# EPS_5V_Buck-Converter.net
KiCad netlist of a schematic drawn in Altium Designer
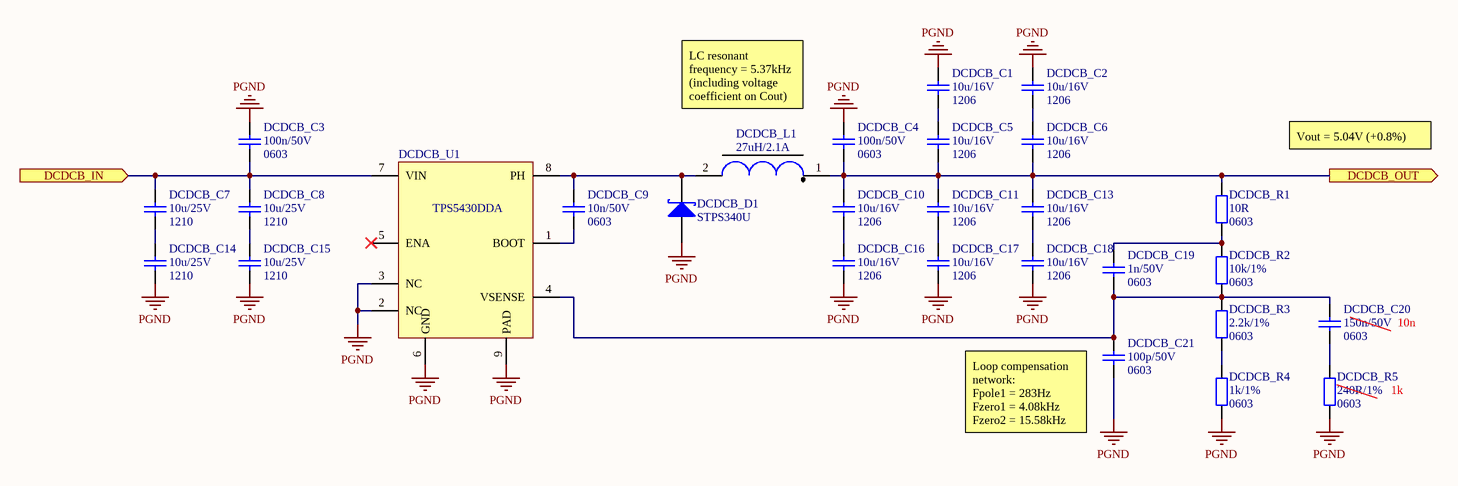
[diagram p0: EPS_5V_Buck-Converter.SchDoc]

(export (version "E")
  (design (tool "Eeschema 10.0.6"))
  (components
    (comp (ref "DCDCB_C1")
      (value "10u/16V")
      (footprint "SMD_Capacitor_1206")
      (description "Ceramic Cap Kemet COTS 10u/16V X7R 1206")
      (fields
        (field (name "MANUFACTURERPARTNUMBER") "C1206T106K4RACTU")
        (field (name "MANUFACTURER") "Kemet")
        (field (name "PACKGE") "1206")
      )
      (libsource (lib "capacitors") (part "Cer_C1206T106K4RACTU"))
    )
    (comp (ref "DCDCB_C2")
      (value "10u/16V")
      (footprint "SMD_Capacitor_1206")
      (description "Ceramic Cap Kemet COTS 10u/16V X7R 1206")
      (fields
        (field (name "MANUFACTURERPARTNUMBER") "C1206T106K4RACTU")
        (field (name "MANUFACTURER") "Kemet")
        (field (name "PACKGE") "1206")
      )
      (libsource (lib "capacitors") (part "Cer_C1206T106K4RACTU"))
    )
    (comp (ref "DCDCB_C3")
      (value "100n/50V")
      (footprint "SMD_Capacitor_0603")
      (description "Ceramic Cap Murata Automotive 100n/50V X7R 0603")
      (fields
        (field (name "MANUFACTURER") "Murata")
        (field (name "MANUFACTURERPARTNUMBER") "GCJ188R71H104KA12D")
        (field (name "PACKAGE") "0603")
      )
      (libsource (lib "capacitors") (part "Cer_GCJ188R71H104KA12D"))
    )
    (comp (ref "DCDCB_C4")
      (value "100n/50V")
      (footprint "SMD_Capacitor_0603")
      (description "Ceramic Cap Murata Automotive 100n/50V X7R 0603")
      (fields
        (field (name "MANUFACTURER") "Murata")
        (field (name "MANUFACTURERPARTNUMBER") "GCJ188R71H104KA12D")
        (field (name "PACKAGE") "0603")
      )
      (libsource (lib "capacitors") (part "Cer_GCJ188R71H104KA12D"))
    )
    (comp (ref "DCDCB_C5")
      (value "10u/16V")
      (footprint "SMD_Capacitor_1206")
      (description "Ceramic Cap Kemet COTS 10u/16V X7R 1206")
      (fields
        (field (name "MANUFACTURERPARTNUMBER") "C1206T106K4RACTU")
        (field (name "MANUFACTURER") "Kemet")
        (field (name "PACKGE") "1206")
      )
      (libsource (lib "capacitors") (part "Cer_C1206T106K4RACTU"))
    )
    (comp (ref "DCDCB_C6")
      (value "10u/16V")
      (footprint "SMD_Capacitor_1206")
      (description "Ceramic Cap Kemet COTS 10u/16V X7R 1206")
      (fields
        (field (name "MANUFACTURERPARTNUMBER") "C1206T106K4RACTU")
        (field (name "MANUFACTURER") "Kemet")
        (field (name "PACKGE") "1206")
      )
      (libsource (lib "capacitors") (part "Cer_C1206T106K4RACTU"))
    )
    (comp (ref "DCDCB_C7")
      (value "10u/25V")
      (footprint "SMD_Capacitor_1210")
      (description "Ceramic Cap Murata Automotive 10u/25V X7R 1210")
      (fields
        (field (name "MANUFACTURER") "Murata")
        (field (name "MANUFACTURERPARTNUMBER") "GCJ32ER71E106KA12L")
        (field (name "PACKAGE") "1210")
      )
      (libsource (lib "capacitors") (part "Cer_GCJ32ER71E106KA12L"))
    )
    (comp (ref "DCDCB_C8")
      (value "10u/25V")
      (footprint "SMD_Capacitor_1210")
      (description "Ceramic Cap Murata Automotive 10u/25V X7R 1210")
      (fields
        (field (name "MANUFACTURER") "Murata")
        (field (name "MANUFACTURERPARTNUMBER") "GCJ32ER71E106KA12L")
        (field (name "PACKAGE") "1210")
      )
      (libsource (lib "capacitors") (part "Cer_GCJ32ER71E106KA12L"))
    )
    (comp (ref "DCDCB_C9")
      (value "10n/50V")
      (footprint "SMD_Capacitor_0603")
      (description "Cap")
      (fields (field (name "PACKAGE") "0603"))
      (libsource (lib "capacitors") (part "Cap"))
    )
    (comp (ref "DCDCB_C10")
      (value "10u/16V")
      (footprint "SMD_Capacitor_1206")
      (description "Ceramic Cap Kemet COTS 10u/16V X7R 1206")
      (fields
        (field (name "MANUFACTURERPARTNUMBER") "C1206T106K4RACTU")
        (field (name "MANUFACTURER") "Kemet")
        (field (name "PACKGE") "1206")
      )
      (libsource (lib "capacitors") (part "Cer_C1206T106K4RACTU"))
    )
    (comp (ref "DCDCB_C11")
      (value "10u/16V")
      (footprint "SMD_Capacitor_1206")
      (description "Ceramic Cap Kemet COTS 10u/16V X7R 1206")
      (fields
        (field (name "MANUFACTURERPARTNUMBER") "C1206T106K4RACTU")
        (field (name "MANUFACTURER") "Kemet")
        (field (name "PACKGE") "1206")
      )
      (libsource (lib "capacitors") (part "Cer_C1206T106K4RACTU"))
    )
    (comp (ref "DCDCB_C13")
      (value "10u/16V")
      (footprint "SMD_Capacitor_1206")
      (description "Ceramic Cap Kemet COTS 10u/16V X7R 1206")
      (fields
        (field (name "MANUFACTURERPARTNUMBER") "C1206T106K4RACTU")
        (field (name "MANUFACTURER") "Kemet")
        (field (name "PACKGE") "1206")
      )
      (libsource (lib "capacitors") (part "Cer_C1206T106K4RACTU"))
    )
    (comp (ref "DCDCB_C14")
      (value "10u/25V")
      (footprint "SMD_Capacitor_1210")
      (description "Ceramic Cap Murata Automotive 10u/25V X7R 1210")
      (fields
        (field (name "MANUFACTURER") "Murata")
        (field (name "MANUFACTURERPARTNUMBER") "GCJ32ER71E106KA12L")
        (field (name "PACKAGE") "1210")
      )
      (libsource (lib "capacitors") (part "Cer_GCJ32ER71E106KA12L"))
    )
    (comp (ref "DCDCB_C15")
      (value "10u/25V")
      (footprint "SMD_Capacitor_1210")
      (description "Ceramic Cap Murata Automotive 10u/25V X7R 1210")
      (fields
        (field (name "MANUFACTURER") "Murata")
        (field (name "MANUFACTURERPARTNUMBER") "GCJ32ER71E106KA12L")
        (field (name "PACKAGE") "1210")
      )
      (libsource (lib "capacitors") (part "Cer_GCJ32ER71E106KA12L"))
    )
    (comp (ref "DCDCB_C16")
      (value "10u/16V")
      (footprint "SMD_Capacitor_1206")
      (description "Ceramic Cap Kemet COTS 10u/16V X7R 1206")
      (fields
        (field (name "MANUFACTURERPARTNUMBER") "C1206T106K4RACTU")
        (field (name "MANUFACTURER") "Kemet")
        (field (name "PACKGE") "1206")
      )
      (libsource (lib "capacitors") (part "Cer_C1206T106K4RACTU"))
    )
    (comp (ref "DCDCB_C17")
      (value "10u/16V")
      (footprint "SMD_Capacitor_1206")
      (description "Ceramic Cap Kemet COTS 10u/16V X7R 1206")
      (fields
        (field (name "MANUFACTURERPARTNUMBER") "C1206T106K4RACTU")
        (field (name "MANUFACTURER") "Kemet")
        (field (name "PACKGE") "1206")
      )
      (libsource (lib "capacitors") (part "Cer_C1206T106K4RACTU"))
    )
    (comp (ref "DCDCB_C18")
      (value "10u/16V")
      (footprint "SMD_Capacitor_1206")
      (description "Ceramic Cap Kemet COTS 10u/16V X7R 1206")
      (fields
        (field (name "MANUFACTURERPARTNUMBER") "C1206T106K4RACTU")
        (field (name "MANUFACTURER") "Kemet")
        (field (name "PACKGE") "1206")
      )
      (libsource (lib "capacitors") (part "Cer_C1206T106K4RACTU"))
    )
    (comp (ref "DCDCB_C19")
      (value "1n/50V")
      (footprint "SMD_Capacitor_0603")
      (description "Cap")
      (fields (field (name "PACKAGE") "0603"))
      (libsource (lib "capacitors") (part "Cap"))
    )
    (comp (ref "DCDCB_C20")
      (value "150n/50V")
      (footprint "SMD_Capacitor_0603")
      (description "Ceramic Cap Murata Automotive 150n/50V X7R 0603")
      (fields
        (field (name "MANUFACTURER") "Murata")
        (field (name "MANUFACTURERPARTNUMBER") "GCM188R71H154KA64D")
        (field (name "PACKAGE") "0603")
      )
      (libsource (lib "capacitors") (part "Cer_GCM188R71H154KA64D"))
    )
    (comp (ref "DCDCB_C21")
      (value "100p/50V")
      (footprint "SMD_Capacitor_0603")
      (description "Cap")
      (fields (field (name "PACKAGE") "0603"))
      (libsource (lib "capacitors") (part "Cap"))
    )
    (comp (ref "DCDCB_D1")
      (value "STPS340U")
      (footprint "DO-214AA")
      (description "3A/40V Power Schottky Rectifier.")
      (fields (field (name "MANUFACTURER") "STMicroelectronics"))
      (libsource (lib "diodes") (part "STPS340x"))
    )
    (comp (ref "DCDCB_L1")
      (value "27uH/2.1A")
      (footprint "Coilcraft_MSS1260")
      (description "Coilcraft MSS1260 Inductor, L=27uH, Irise20deg=2.1A, ESR=50mR, SRF=13MHz.")
      (fields
        (field (name "MANUFACTURER") "Coilcraft")
        (field (name "MANUFACTURERPARTNUMBER") "MSS1260-273MLx")
      )
      (libsource (lib "inductors") (part "MSS1260-273MLx"))
    )
    (comp (ref "DCDCB_R1")
      (value "10R")
      (footprint "SMD_Resistor_0603")
      (fields (field (name "PACKAGE") "0603"))
      (libsource (lib "resistors") (part "Res"))
    )
    (comp (ref "DCDCB_R2")
      (value "10k/1%")
      (footprint "SMD_Resistor_0603")
      (fields (field (name "PACKAGE") "0603"))
      (libsource (lib "resistors") (part "Res"))
    )
    (comp (ref "DCDCB_R3")
      (value "2.2k/1%")
      (footprint "SMD_Resistor_0603")
      (fields (field (name "PACKAGE") "0603"))
      (libsource (lib "resistors") (part "Res"))
    )
    (comp (ref "DCDCB_R4")
      (value "1k/1%")
      (footprint "SMD_Resistor_0603")
      (fields (field (name "PACKAGE") "0603"))
      (libsource (lib "resistors") (part "Res"))
    )
    (comp (ref "DCDCB_R5")
      (value "240R/1%")
      (footprint "SMD_Resistor_0603")
      (fields (field (name "PACKAGE") "0603"))
      (libsource (lib "resistors") (part "Res"))
    )
    (comp (ref "DCDCB_U1")
      (value "TPS5430DDA")
      (footprint "DDA-9")
      (description "TPS5430 3-A, Wide Input Range, Step-Down Converter")
      (fields (field (name "MANUFACTURER") "Texas Instruments"))
      (libsource (lib "microcircuits") (part "TPS5430"))
    )
  )
  (nets
    (net (code "1") (name "/DCDCB_IN") (class "Default")
      (node (ref "DCDCB_C3") (pin "1") (pinfunction "1_1") (pintype "passive"))
      (node (ref "DCDCB_C7") (pin "1") (pinfunction "1_1") (pintype "passive"))
      (node (ref "DCDCB_C8") (pin "1") (pinfunction "1_1") (pintype "passive"))
      (node (ref "DCDCB_U1") (pin "7") (pinfunction "VIN_7") (pintype "passive"))
    )
    (net (code "2") (name "/DCDCB_OUT") (class "Default")
      (node (ref "DCDCB_C10") (pin "1") (pinfunction "1_1") (pintype "passive"))
      (node (ref "DCDCB_C11") (pin "1") (pinfunction "1_1") (pintype "passive"))
      (node (ref "DCDCB_C13") (pin "1") (pinfunction "1_1") (pintype "passive"))
      (node (ref "DCDCB_C4") (pin "1") (pinfunction "1_1") (pintype "passive"))
      (node (ref "DCDCB_C5") (pin "2") (pinfunction "2_2") (pintype "passive"))
      (node (ref "DCDCB_C6") (pin "2") (pinfunction "2_2") (pintype "passive"))
      (node (ref "DCDCB_L1") (pin "1") (pinfunction "1_1") (pintype "passive"))
      (node (ref "DCDCB_R1") (pin "2") (pinfunction "2_2") (pintype "passive"))
    )
    (net (code "3") (name "Net-(DCDCB_C1-Pad2)") (class "Default")
      (node (ref "DCDCB_C1") (pin "2") (pinfunction "2_2") (pintype "passive"))
      (node (ref "DCDCB_C5") (pin "1") (pinfunction "1_1") (pintype "passive"))
    )
    (net (code "4") (name "Net-(DCDCB_C2-Pad2)") (class "Default")
      (node (ref "DCDCB_C2") (pin "2") (pinfunction "2_2") (pintype "passive"))
      (node (ref "DCDCB_C6") (pin "1") (pinfunction "1_1") (pintype "passive"))
    )
    (net (code "5") (name "Net-(DCDCB_C10-Pad2)") (class "Default")
      (node (ref "DCDCB_C10") (pin "2") (pinfunction "2_2") (pintype "passive"))
      (node (ref "DCDCB_C16") (pin "1") (pinfunction "1_1") (pintype "passive"))
    )
    (net (code "6") (name "Net-(DCDCB_C11-Pad2)") (class "Default")
      (node (ref "DCDCB_C11") (pin "2") (pinfunction "2_2") (pintype "passive"))
      (node (ref "DCDCB_C17") (pin "1") (pinfunction "1_1") (pintype "passive"))
    )
    (net (code "7") (name "Net-(DCDCB_C13-Pad2)") (class "Default")
      (node (ref "DCDCB_C13") (pin "2") (pinfunction "2_2") (pintype "passive"))
      (node (ref "DCDCB_C18") (pin "1") (pinfunction "1_1") (pintype "passive"))
    )
    (net (code "8") (name "Net-(DCDCB_C14-Pad1)") (class "Default")
      (node (ref "DCDCB_C14") (pin "1") (pinfunction "1_1") (pintype "passive"))
      (node (ref "DCDCB_C7") (pin "2") (pinfunction "2_2") (pintype "passive"))
    )
    (net (code "9") (name "Net-(DCDCB_C15-Pad1)") (class "Default")
      (node (ref "DCDCB_C15") (pin "1") (pinfunction "1_1") (pintype "passive"))
      (node (ref "DCDCB_C8") (pin "2") (pinfunction "2_2") (pintype "passive"))
    )
    (net (code "10") (name "Net-(DCDCB_C19-Pad1)") (class "Default")
      (node (ref "DCDCB_C19") (pin "1") (pinfunction "1_1") (pintype "passive"))
      (node (ref "DCDCB_R1") (pin "1") (pinfunction "1_1") (pintype "passive"))
      (node (ref "DCDCB_R2") (pin "2") (pinfunction "2_2") (pintype "passive"))
    )
    (net (code "11") (name "Net-(DCDCB_C20-Pad2)") (class "Default")
      (node (ref "DCDCB_C20") (pin "2") (pinfunction "2_2") (pintype "passive"))
      (node (ref "DCDCB_R5") (pin "2") (pinfunction "2_2") (pintype "passive"))
    )
    (net (code "12") (name "Net-(DCDCB_R3-Pad1)") (class "Default")
      (node (ref "DCDCB_R3") (pin "1") (pinfunction "1_1") (pintype "passive"))
      (node (ref "DCDCB_R4") (pin "2") (pinfunction "2_2") (pintype "passive"))
    )
    (net (code "13") (name "Net-(DCDCB_U1-BOOT)") (class "Default")
      (node (ref "DCDCB_C9") (pin "2") (pinfunction "2_2") (pintype "passive"))
      (node (ref "DCDCB_U1") (pin "1") (pinfunction "BOOT_1") (pintype "passive"))
    )
    (net (code "14") (name "Net-(DCDCB_U1-PH)") (class "Default")
      (node (ref "DCDCB_C9") (pin "1") (pinfunction "1_1") (pintype "passive"))
      (node (ref "DCDCB_D1") (pin "K") (pinfunction "K_K") (pintype "passive"))
      (node (ref "DCDCB_L1") (pin "2") (pinfunction "2_2") (pintype "passive"))
      (node (ref "DCDCB_U1") (pin "8") (pinfunction "PH_8") (pintype "passive"))
    )
    (net (code "15") (name "Net-(DCDCB_U1-VSENSE)") (class "Default")
      (node (ref "DCDCB_C19") (pin "2") (pinfunction "2_2") (pintype "passive"))
      (node (ref "DCDCB_C20") (pin "1") (pinfunction "1_1") (pintype "passive"))
      (node (ref "DCDCB_C21") (pin "1") (pinfunction "1_1") (pintype "passive"))
      (node (ref "DCDCB_R2") (pin "1") (pinfunction "1_1") (pintype "passive"))
      (node (ref "DCDCB_R3") (pin "2") (pinfunction "2_2") (pintype "passive"))
      (node (ref "DCDCB_U1") (pin "4") (pinfunction "VSENSE_4") (pintype "passive"))
    )
    (net (code "16") (name "PGND") (class "Default")
      (node (ref "DCDCB_C1") (pin "1") (pinfunction "1_1") (pintype "passive"))
      (node (ref "DCDCB_C14") (pin "2") (pinfunction "2_2") (pintype "passive"))
      (node (ref "DCDCB_C15") (pin "2") (pinfunction "2_2") (pintype "passive"))
      (node (ref "DCDCB_C16") (pin "2") (pinfunction "2_2") (pintype "passive"))
      (node (ref "DCDCB_C17") (pin "2") (pinfunction "2_2") (pintype "passive"))
      (node (ref "DCDCB_C18") (pin "2") (pinfunction "2_2") (pintype "passive"))
      (node (ref "DCDCB_C2") (pin "1") (pinfunction "1_1") (pintype "passive"))
      (node (ref "DCDCB_C21") (pin "2") (pinfunction "2_2") (pintype "passive"))
      (node (ref "DCDCB_C3") (pin "2") (pinfunction "2_2") (pintype "passive"))
      (node (ref "DCDCB_C4") (pin "2") (pinfunction "2_2") (pintype "passive"))
      (node (ref "DCDCB_D1") (pin "A") (pinfunction "A_A") (pintype "passive"))
      (node (ref "DCDCB_R4") (pin "1") (pinfunction "1_1") (pintype "passive"))
      (node (ref "DCDCB_R5") (pin "1") (pinfunction "1_1") (pintype "passive"))
      (node (ref "DCDCB_U1") (pin "2") (pinfunction "NC_2") (pintype "passive"))
      (node (ref "DCDCB_U1") (pin "3") (pinfunction "NC_3") (pintype "passive"))
      (node (ref "DCDCB_U1") (pin "6") (pinfunction "GND_6") (pintype "passive"))
      (node (ref "DCDCB_U1") (pin "9") (pinfunction "PAD_9") (pintype "passive"))
    )
    (net (code "17") (name "unconnected-(DCDCB_U1-ENA-Pad5)") (class "Default")
      (node (ref "DCDCB_U1") (pin "5") (pinfunction "ENA_5") (pintype "passive+no_connect"))
    )
  )
)
